# IO_Level_Shifters.net
KiCad netlist of a schematic drawn in Altium Designer
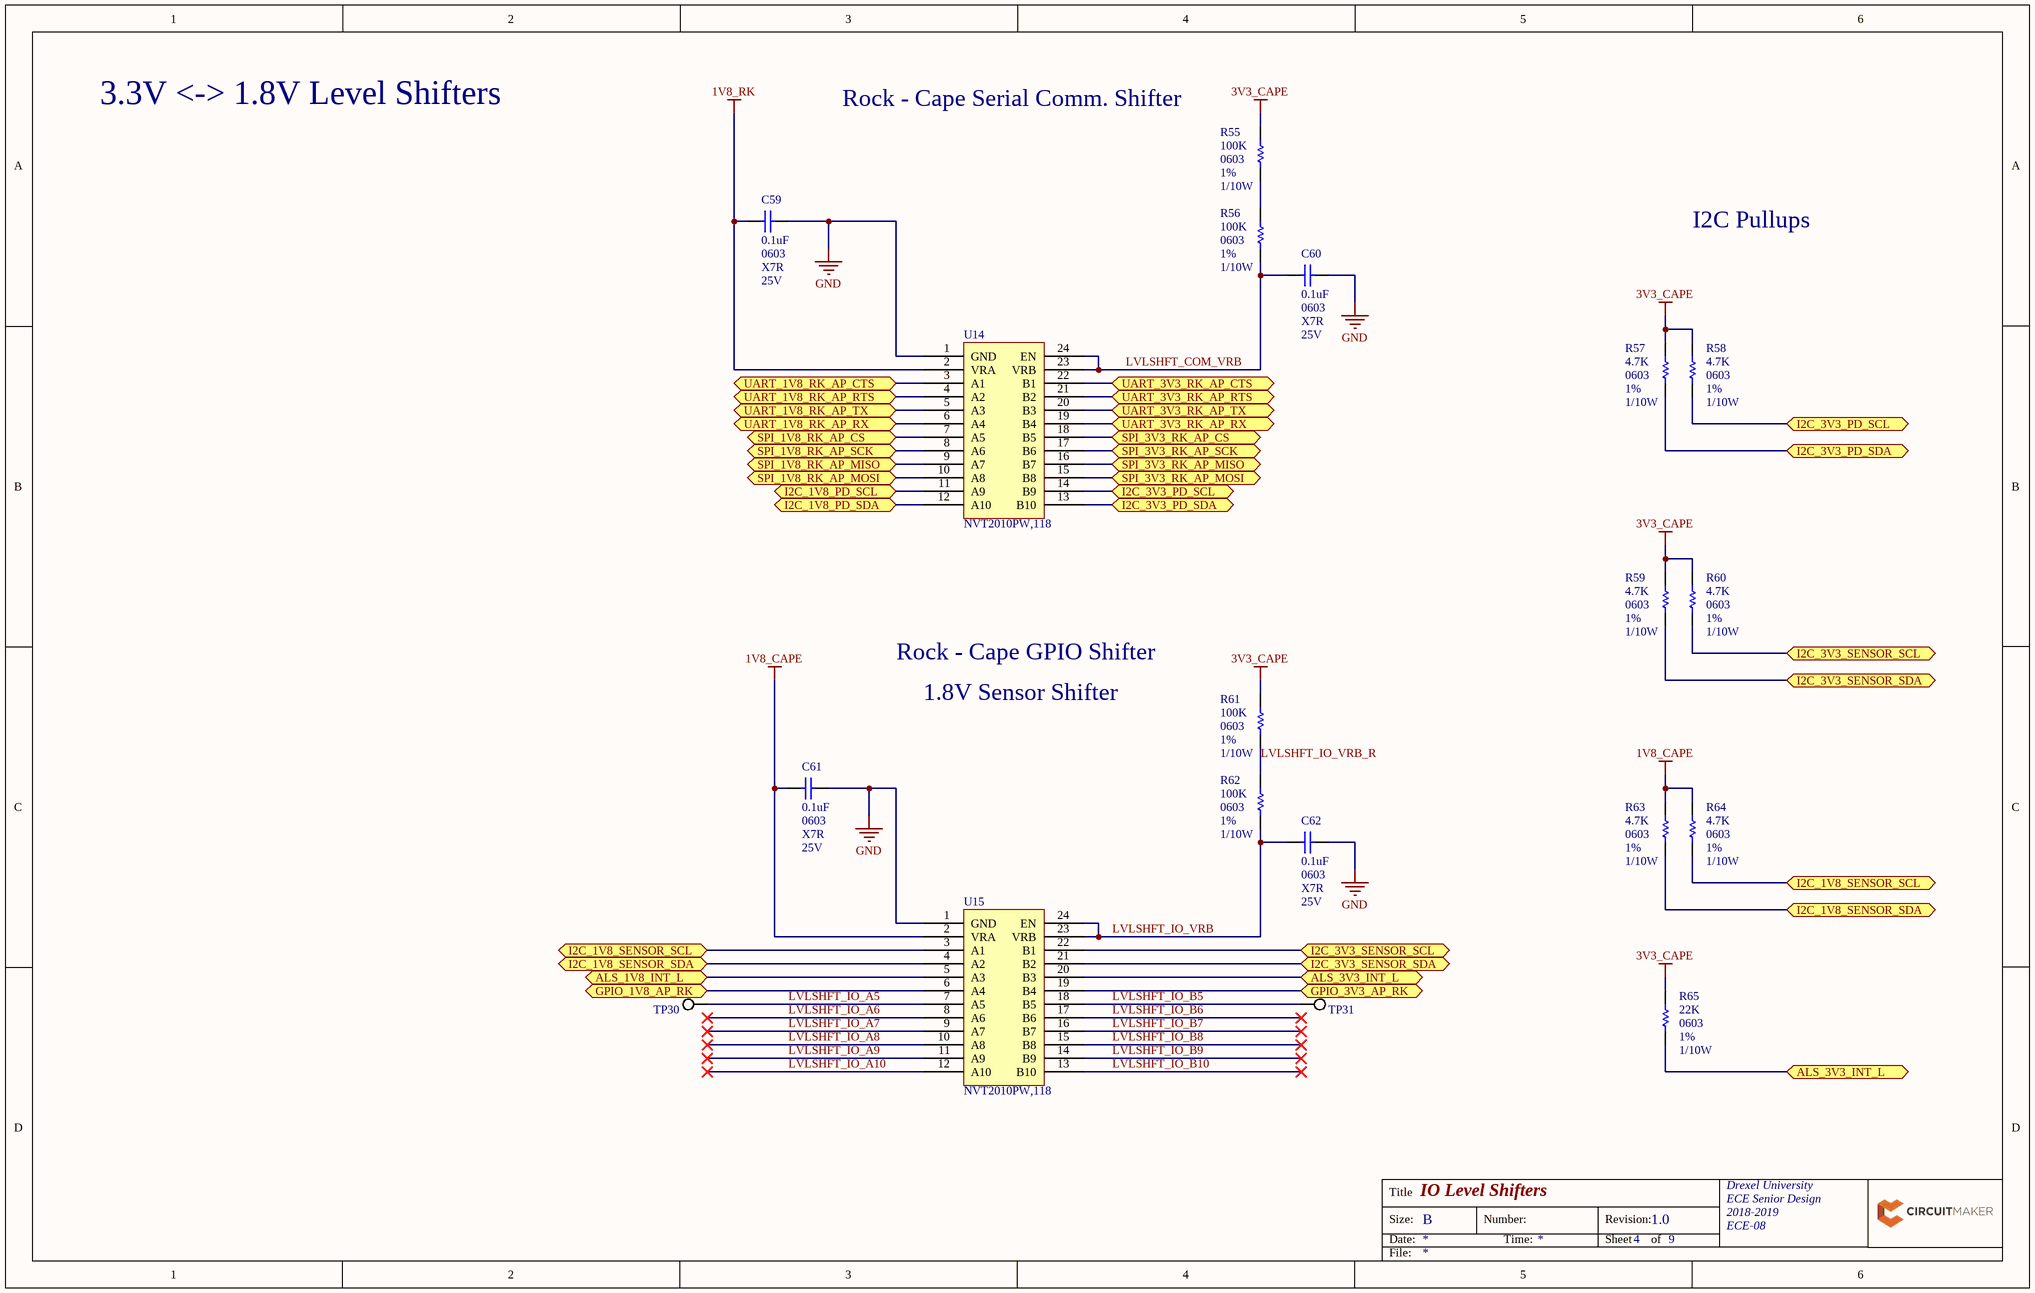
[diagram p0: IO Level Shifters.SchDoc]

(export (version "E")
  (design (tool "Eeschema 10.0.6"))
  (components
    (comp (ref "C59")
      (value "Würth Elektronik 885012206071")
      (footprint "PCB-8usp83j76ntw2xroyu3n-1")
      (description "Multilayer Ceramic Capacitor, WCAP-CSGP Series, 0.1 F, 10%, X7R, 25 V, 0603 [1608 Metric]")
      (fields
        (field (name "DIELECTRIC CHARACTERISTIC") "X7R")
        (field (name "VOLTAGE RATING (DC)") "25V")
        (field (name "CAPACITANCE") "0.1uF")
        (field (name "MANUFACTURER PART NUMBER") "885012206071")
        (field (name "PACKAGE") "0603")
      )
      (libsource (lib "CommunityVault") (part "CMP-034ac9768ab0dc8d-1"))
    )
    (comp (ref "C60")
      (value "Würth Elektronik 885012206071")
      (footprint "PCB-8usp83j76ntw2xroyu3n-1")
      (description "Multilayer Ceramic Capacitor, WCAP-CSGP Series, 0.1 F, 10%, X7R, 25 V, 0603 [1608 Metric]")
      (fields
        (field (name "DIELECTRIC CHARACTERISTIC") "X7R")
        (field (name "VOLTAGE RATING (DC)") "25V")
        (field (name "CAPACITANCE") "0.1uF")
        (field (name "MANUFACTURER PART NUMBER") "885012206071")
        (field (name "PACKAGE") "0603")
      )
      (libsource (lib "CommunityVault") (part "CMP-034ac9768ab0dc8d-1"))
    )
    (comp (ref "C61")
      (value "Würth Elektronik 885012206071")
      (footprint "PCB-8usp83j76ntw2xroyu3n-1")
      (description "Multilayer Ceramic Capacitor, WCAP-CSGP Series, 0.1 F, 10%, X7R, 25 V, 0603 [1608 Metric]")
      (fields
        (field (name "DIELECTRIC CHARACTERISTIC") "X7R")
        (field (name "VOLTAGE RATING (DC)") "25V")
        (field (name "CAPACITANCE") "0.1uF")
        (field (name "MANUFACTURER PART NUMBER") "885012206071")
        (field (name "PACKAGE") "0603")
      )
      (libsource (lib "CommunityVault") (part "CMP-034ac9768ab0dc8d-1"))
    )
    (comp (ref "C62")
      (value "Würth Elektronik 885012206071")
      (footprint "PCB-8usp83j76ntw2xroyu3n-1")
      (description "Multilayer Ceramic Capacitor, WCAP-CSGP Series, 0.1 F, 10%, X7R, 25 V, 0603 [1608 Metric]")
      (fields
        (field (name "DIELECTRIC CHARACTERISTIC") "X7R")
        (field (name "VOLTAGE RATING (DC)") "25V")
        (field (name "CAPACITANCE") "0.1uF")
        (field (name "MANUFACTURER PART NUMBER") "885012206071")
        (field (name "PACKAGE") "0603")
      )
      (libsource (lib "CommunityVault") (part "CMP-034ac9768ab0dc8d-1"))
    )
    (comp (ref "R55")
      (value "Res1")
      (footprint "PCB-js3e944hkesj3cskg8px-1")
      (description "Res Thick Film 0603 100K Ohm 1% 0.1W(1/10W) ±100ppm/C Pad SMD T/R")
      (fields
        (field (name "RESISTANCE") "100K")
        (field (name "POWER RATING") "1/10W")
        (field (name "PACKAGE") "0603")
        (field (name "TOLERANCE") "1%")
      )
      (libsource (lib "CommunityVault") (part "CMP-47e38e6423219824-1"))
    )
    (comp (ref "R56")
      (value "Res1")
      (footprint "PCB-js3e944hkesj3cskg8px-1")
      (description "Res Thick Film 0603 100K Ohm 1% 0.1W(1/10W) ±100ppm/C Pad SMD T/R")
      (fields
        (field (name "RESISTANCE") "100K")
        (field (name "POWER RATING") "1/10W")
        (field (name "PACKAGE") "0603")
        (field (name "TOLERANCE") "1%")
      )
      (libsource (lib "CommunityVault") (part "CMP-47e38e6423219824-1"))
    )
    (comp (ref "R57")
      (value "4k7")
      (footprint "CAPC1608X90X35NL15T15")
      (description "Res Thick Film 0603 4.7K Ohm 1% 1/10W ±100ppm/°C Molded SMD SMD Paper Tape on Plastic Reel")
      (fields
        (field (name "RESISTANCE") "4.7K")
        (field (name "PACKAGE") "0603")
        (field (name "POWER RATING") "1/10W")
        (field (name "TOLERANCE") "1%")
      )
      (libsource (lib "CommunityVault") (part "CMP-3ca7f596181de360-9"))
    )
    (comp (ref "R58")
      (value "4k7")
      (footprint "CAPC1608X90X35NL15T15")
      (description "Res Thick Film 0603 4.7K Ohm 1% 1/10W ±100ppm/°C Molded SMD SMD Paper Tape on Plastic Reel")
      (fields
        (field (name "RESISTANCE") "4.7K")
        (field (name "PACKAGE") "0603")
        (field (name "POWER RATING") "1/10W")
        (field (name "TOLERANCE") "1%")
      )
      (libsource (lib "CommunityVault") (part "CMP-3ca7f596181de360-9"))
    )
    (comp (ref "R59")
      (value "4k7")
      (footprint "CAPC1608X90X35NL15T15")
      (description "Res Thick Film 0603 4.7K Ohm 1% 1/10W ±100ppm/°C Molded SMD SMD Paper Tape on Plastic Reel")
      (fields
        (field (name "RESISTANCE") "4.7K")
        (field (name "PACKAGE") "0603")
        (field (name "POWER RATING") "1/10W")
        (field (name "TOLERANCE") "1%")
      )
      (libsource (lib "CommunityVault") (part "CMP-3ca7f596181de360-9"))
    )
    (comp (ref "R60")
      (value "4k7")
      (footprint "CAPC1608X90X35NL15T15")
      (description "Res Thick Film 0603 4.7K Ohm 1% 1/10W ±100ppm/°C Molded SMD SMD Paper Tape on Plastic Reel")
      (fields
        (field (name "RESISTANCE") "4.7K")
        (field (name "PACKAGE") "0603")
        (field (name "POWER RATING") "1/10W")
        (field (name "TOLERANCE") "1%")
      )
      (libsource (lib "CommunityVault") (part "CMP-3ca7f596181de360-9"))
    )
    (comp (ref "R61")
      (value "Res1")
      (footprint "PCB-js3e944hkesj3cskg8px-1")
      (description "Res Thick Film 0603 100K Ohm 1% 0.1W(1/10W) ±100ppm/C Pad SMD T/R")
      (fields
        (field (name "RESISTANCE") "100K")
        (field (name "POWER RATING") "1/10W")
        (field (name "PACKAGE") "0603")
        (field (name "TOLERANCE") "1%")
      )
      (libsource (lib "CommunityVault") (part "CMP-47e38e6423219824-1"))
    )
    (comp (ref "R62")
      (value "Res1")
      (footprint "PCB-js3e944hkesj3cskg8px-1")
      (description "Res Thick Film 0603 100K Ohm 1% 0.1W(1/10W) ±100ppm/C Pad SMD T/R")
      (fields
        (field (name "RESISTANCE") "100K")
        (field (name "POWER RATING") "1/10W")
        (field (name "PACKAGE") "0603")
        (field (name "TOLERANCE") "1%")
      )
      (libsource (lib "CommunityVault") (part "CMP-47e38e6423219824-1"))
    )
    (comp (ref "R63")
      (value "4k7")
      (footprint "CAPC1608X90X35NL15T15")
      (description "Res Thick Film 0603 4.7K Ohm 1% 1/10W ±100ppm/°C Molded SMD SMD Paper Tape on Plastic Reel")
      (fields
        (field (name "RESISTANCE") "4.7K")
        (field (name "PACKAGE") "0603")
        (field (name "POWER RATING") "1/10W")
        (field (name "TOLERANCE") "1%")
      )
      (libsource (lib "CommunityVault") (part "CMP-3ca7f596181de360-9"))
    )
    (comp (ref "R64")
      (value "4k7")
      (footprint "CAPC1608X90X35NL15T15")
      (description "Res Thick Film 0603 4.7K Ohm 1% 1/10W ±100ppm/°C Molded SMD SMD Paper Tape on Plastic Reel")
      (fields
        (field (name "RESISTANCE") "4.7K")
        (field (name "PACKAGE") "0603")
        (field (name "POWER RATING") "1/10W")
        (field (name "TOLERANCE") "1%")
      )
      (libsource (lib "CommunityVault") (part "CMP-3ca7f596181de360-9"))
    )
    (comp (ref "R65")
      (value "Yageo RC0603FR-0722KL")
      (footprint "RESC1608X55X25LL10T15")
      (description "Chip Resistor, 22 KOhm, +/- 1%, 0.1 W, -55 to 155 degC, 0603 (1608 Metric), RoHS, Tape and Reel")
      (fields
        (field (name "RESISTANCE") "22K")
        (field (name "RESISTANCE TOLERANCE") "1%")
        (field (name "CASE/PACKAGE") "0603")
        (field (name "POWER RATING") "1/10W")
        (field (name "MANUFACTURER PART NUMBER") "RC0603FR-0722KL")
      )
      (libsource (lib "CommunityVault") (part "CMP-1853446-5"))
    )
    (comp (ref "TP30")
      (value "SYM-r3tntvff39g057zxjnnx-1")
      (footprint "PCB-hew5anfrhkqvtgt23eko-1")
      (description "SMT Pad Test Point 1.27mm Diameter")
      (libsource (lib "CommunityVault") (part "SYM-r3tntvff39g057zxjnnx-1"))
    )
    (comp (ref "TP31")
      (value "SYM-r3tntvff39g057zxjnnx-1")
      (footprint "PCB-hew5anfrhkqvtgt23eko-1")
      (description "SMT Pad Test Point 1.27mm Diameter")
      (libsource (lib "CommunityVault") (part "SYM-r3tntvff39g057zxjnnx-1"))
    )
    (comp (ref "U14")
      (value "NVT2010PW,118")
      (footprint "PCBComponent_1 - duplicate")
      (description "Voltage Level Translator 24-Pin TSSOP T/R")
      (libsource (lib "CommunityVault") (part "CMP-e872205300dc37b5-1"))
    )
    (comp (ref "U15")
      (value "NVT2010PW,118")
      (footprint "PCBComponent_1 - duplicate")
      (description "Voltage Level Translator 24-Pin TSSOP T/R")
      (libsource (lib "CommunityVault") (part "CMP-e872205300dc37b5-1"))
    )
  )
  (nets
    (net (code "1") (name "/ALS_1V8_INT_L") (class "Default")
      (node (ref "U15") (pin "5") (pinfunction "A3_5") (pintype "passive"))
    )
    (net (code "2") (name "/ALS_3V3_INT_L") (class "Default")
      (node (ref "R65") (pin "1") (pinfunction "1_1") (pintype "passive"))
      (node (ref "U15") (pin "20") (pinfunction "B3_20") (pintype "passive"))
    )
    (net (code "3") (name "/GPIO_1V8_AP_RK") (class "Default")
      (node (ref "U15") (pin "6") (pinfunction "A4_6") (pintype "passive"))
    )
    (net (code "4") (name "/GPIO_3V3_AP_RK") (class "Default")
      (node (ref "U15") (pin "19") (pinfunction "B4_19") (pintype "passive"))
    )
    (net (code "5") (name "/I2C_1V8_PD_SCL") (class "Default")
      (node (ref "U14") (pin "11") (pinfunction "A9_11") (pintype "passive"))
    )
    (net (code "6") (name "/I2C_1V8_PD_SDA") (class "Default")
      (node (ref "U14") (pin "12") (pinfunction "A10_12") (pintype "passive"))
    )
    (net (code "7") (name "/I2C_1V8_SENSOR_SCL") (class "Default")
      (node (ref "R64") (pin "1") (pinfunction "1_1") (pintype "passive"))
      (node (ref "U15") (pin "3") (pinfunction "A1_3") (pintype "passive"))
    )
    (net (code "8") (name "/I2C_1V8_SENSOR_SDA") (class "Default")
      (node (ref "R63") (pin "1") (pinfunction "1_1") (pintype "passive"))
      (node (ref "U15") (pin "4") (pinfunction "A2_4") (pintype "passive"))
    )
    (net (code "9") (name "/I2C_3V3_PD_SCL") (class "Default")
      (node (ref "R58") (pin "1") (pinfunction "1_1") (pintype "passive"))
      (node (ref "U14") (pin "14") (pinfunction "B9_14") (pintype "passive"))
    )
    (net (code "10") (name "/I2C_3V3_PD_SDA") (class "Default")
      (node (ref "R57") (pin "1") (pinfunction "1_1") (pintype "passive"))
      (node (ref "U14") (pin "13") (pinfunction "B10_13") (pintype "passive"))
    )
    (net (code "11") (name "/I2C_3V3_SENSOR_SCL") (class "Default")
      (node (ref "R60") (pin "1") (pinfunction "1_1") (pintype "passive"))
      (node (ref "U15") (pin "22") (pinfunction "B1_22") (pintype "passive"))
    )
    (net (code "12") (name "/I2C_3V3_SENSOR_SDA") (class "Default")
      (node (ref "R59") (pin "1") (pinfunction "1_1") (pintype "passive"))
      (node (ref "U15") (pin "21") (pinfunction "B2_21") (pintype "passive"))
    )
    (net (code "13") (name "/LVLSHFT_COM_VRB") (class "Default")
      (node (ref "C60") (pin "1") (pinfunction "1_1") (pintype "passive"))
      (node (ref "R56") (pin "1") (pinfunction "1_1") (pintype "passive"))
      (node (ref "U14") (pin "23") (pinfunction "VRB_23") (pintype "power_in"))
      (node (ref "U14") (pin "24") (pinfunction "EN_24") (pintype "passive"))
    )
    (net (code "14") (name "/LVLSHFT_IO_A5") (class "Default")
      (node (ref "TP30") (pin "1") (pinfunction "1_1") (pintype "passive"))
      (node (ref "U15") (pin "7") (pinfunction "A5_7") (pintype "passive"))
    )
    (net (code "15") (name "/LVLSHFT_IO_A6") (class "Default")
      (node (ref "U15") (pin "8") (pinfunction "A6_8") (pintype "passive+no_connect"))
    )
    (net (code "16") (name "/LVLSHFT_IO_A7") (class "Default")
      (node (ref "U15") (pin "9") (pinfunction "A7_9") (pintype "passive+no_connect"))
    )
    (net (code "17") (name "/LVLSHFT_IO_A8") (class "Default")
      (node (ref "U15") (pin "10") (pinfunction "A8_10") (pintype "passive+no_connect"))
    )
    (net (code "18") (name "/LVLSHFT_IO_A9") (class "Default")
      (node (ref "U15") (pin "11") (pinfunction "A9_11") (pintype "passive+no_connect"))
    )
    (net (code "19") (name "/LVLSHFT_IO_A10") (class "Default")
      (node (ref "U15") (pin "12") (pinfunction "A10_12") (pintype "passive+no_connect"))
    )
    (net (code "20") (name "/LVLSHFT_IO_B5") (class "Default")
      (node (ref "TP31") (pin "1") (pinfunction "1_1") (pintype "passive"))
      (node (ref "U15") (pin "18") (pinfunction "B5_18") (pintype "passive"))
    )
    (net (code "21") (name "/LVLSHFT_IO_B6") (class "Default")
      (node (ref "U15") (pin "17") (pinfunction "B6_17") (pintype "passive+no_connect"))
    )
    (net (code "22") (name "/LVLSHFT_IO_B7") (class "Default")
      (node (ref "U15") (pin "16") (pinfunction "B7_16") (pintype "passive+no_connect"))
    )
    (net (code "23") (name "/LVLSHFT_IO_B8") (class "Default")
      (node (ref "U15") (pin "15") (pinfunction "B8_15") (pintype "passive+no_connect"))
    )
    (net (code "24") (name "/LVLSHFT_IO_B9") (class "Default")
      (node (ref "U15") (pin "14") (pinfunction "B9_14") (pintype "passive+no_connect"))
    )
    (net (code "25") (name "/LVLSHFT_IO_B10") (class "Default")
      (node (ref "U15") (pin "13") (pinfunction "B10_13") (pintype "passive+no_connect"))
    )
    (net (code "26") (name "/LVLSHFT_IO_VRB") (class "Default")
      (node (ref "C62") (pin "1") (pinfunction "1_1") (pintype "passive"))
      (node (ref "R62") (pin "1") (pinfunction "1_1") (pintype "passive"))
      (node (ref "U15") (pin "23") (pinfunction "VRB_23") (pintype "power_in"))
      (node (ref "U15") (pin "24") (pinfunction "EN_24") (pintype "passive"))
    )
    (net (code "27") (name "/LVLSHFT_IO_VRB_R") (class "Default")
      (node (ref "R61") (pin "1") (pinfunction "1_1") (pintype "passive"))
      (node (ref "R62") (pin "2") (pinfunction "2_2") (pintype "passive"))
    )
    (net (code "28") (name "/SPI_1V8_RK_AP_CS") (class "Default")
      (node (ref "U14") (pin "7") (pinfunction "A5_7") (pintype "passive"))
    )
    (net (code "29") (name "/SPI_1V8_RK_AP_MISO") (class "Default")
      (node (ref "U14") (pin "9") (pinfunction "A7_9") (pintype "passive"))
    )
    (net (code "30") (name "/SPI_1V8_RK_AP_MOSI") (class "Default")
      (node (ref "U14") (pin "10") (pinfunction "A8_10") (pintype "passive"))
    )
    (net (code "31") (name "/SPI_1V8_RK_AP_SCK") (class "Default")
      (node (ref "U14") (pin "8") (pinfunction "A6_8") (pintype "passive"))
    )
    (net (code "32") (name "/SPI_3V3_RK_AP_CS") (class "Default")
      (node (ref "U14") (pin "18") (pinfunction "B5_18") (pintype "passive"))
    )
    (net (code "33") (name "/SPI_3V3_RK_AP_MISO") (class "Default")
      (node (ref "U14") (pin "16") (pinfunction "B7_16") (pintype "passive"))
    )
    (net (code "34") (name "/SPI_3V3_RK_AP_MOSI") (class "Default")
      (node (ref "U14") (pin "15") (pinfunction "B8_15") (pintype "passive"))
    )
    (net (code "35") (name "/SPI_3V3_RK_AP_SCK") (class "Default")
      (node (ref "U14") (pin "17") (pinfunction "B6_17") (pintype "passive"))
    )
    (net (code "36") (name "/UART_1V8_RK_AP_CTS") (class "Default")
      (node (ref "U14") (pin "3") (pinfunction "A1_3") (pintype "passive"))
    )
    (net (code "37") (name "/UART_1V8_RK_AP_RTS") (class "Default")
      (node (ref "U14") (pin "4") (pinfunction "A2_4") (pintype "passive"))
    )
    (net (code "38") (name "/UART_1V8_RK_AP_RX") (class "Default")
      (node (ref "U14") (pin "6") (pinfunction "A4_6") (pintype "passive"))
    )
    (net (code "39") (name "/UART_1V8_RK_AP_TX") (class "Default")
      (node (ref "U14") (pin "5") (pinfunction "A3_5") (pintype "passive"))
    )
    (net (code "40") (name "/UART_3V3_RK_AP_CTS") (class "Default")
      (node (ref "U14") (pin "22") (pinfunction "B1_22") (pintype "passive"))
    )
    (net (code "41") (name "/UART_3V3_RK_AP_RTS") (class "Default")
      (node (ref "U14") (pin "21") (pinfunction "B2_21") (pintype "passive"))
    )
    (net (code "42") (name "/UART_3V3_RK_AP_RX") (class "Default")
      (node (ref "U14") (pin "19") (pinfunction "B4_19") (pintype "passive"))
    )
    (net (code "43") (name "/UART_3V3_RK_AP_TX") (class "Default")
      (node (ref "U14") (pin "20") (pinfunction "B3_20") (pintype "passive"))
    )
    (net (code "44") (name "1V8_CAPE") (class "Default")
      (node (ref "C61") (pin "1") (pinfunction "1_1") (pintype "passive"))
      (node (ref "R63") (pin "2") (pinfunction "2_2") (pintype "passive"))
      (node (ref "R64") (pin "2") (pinfunction "2_2") (pintype "passive"))
      (node (ref "U15") (pin "2") (pinfunction "VRA_2") (pintype "power_in"))
    )
    (net (code "45") (name "1V8_RK") (class "Default")
      (node (ref "C59") (pin "1") (pinfunction "1_1") (pintype "passive"))
      (node (ref "U14") (pin "2") (pinfunction "VRA_2") (pintype "power_in"))
    )
    (net (code "46") (name "3V3_CAPE") (class "Default")
      (node (ref "R55") (pin "2") (pinfunction "2_2") (pintype "passive"))
      (node (ref "R57") (pin "2") (pinfunction "2_2") (pintype "passive"))
      (node (ref "R58") (pin "2") (pinfunction "2_2") (pintype "passive"))
      (node (ref "R59") (pin "2") (pinfunction "2_2") (pintype "passive"))
      (node (ref "R60") (pin "2") (pinfunction "2_2") (pintype "passive"))
      (node (ref "R61") (pin "2") (pinfunction "2_2") (pintype "passive"))
      (node (ref "R65") (pin "2") (pinfunction "2_2") (pintype "passive"))
    )
    (net (code "47") (name "GND") (class "Default")
      (node (ref "C59") (pin "2") (pinfunction "2_2") (pintype "passive"))
      (node (ref "C60") (pin "2") (pinfunction "2_2") (pintype "passive"))
      (node (ref "C61") (pin "2") (pinfunction "2_2") (pintype "passive"))
      (node (ref "C62") (pin "2") (pinfunction "2_2") (pintype "passive"))
      (node (ref "U14") (pin "1") (pinfunction "GND_1") (pintype "power_in"))
      (node (ref "U15") (pin "1") (pinfunction "GND_1") (pintype "power_in"))
    )
    (net (code "48") (name "Net-(R55-Pad1)") (class "Default")
      (node (ref "R55") (pin "1") (pinfunction "1_1") (pintype "passive"))
      (node (ref "R56") (pin "2") (pinfunction "2_2") (pintype "passive"))
    )
  )
)
